# 48V_0_5A_Converter.net
KiCad netlist of a schematic drawn in Altium Designer
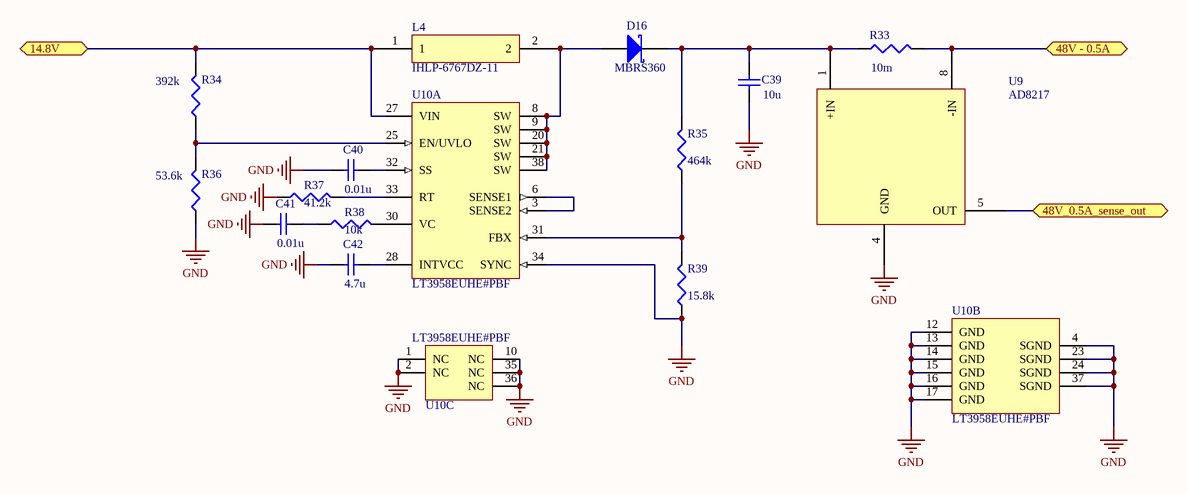
[diagram p0: 48V_0.5A_Converter.SchDoc]

(export (version "E")
  (design (tool "Eeschema 10.0.6"))
  (components
    (comp (ref "C39")
      (value "10u")
      (footprint "C1206")
      (description "Capacitor (Semiconductor SIM Model)")
      (fields (field (name "Comment") "Cap Semi") (field (name "PUBLISHER") "Altium Limited"))
      (libsource (lib "Miscellaneous Devices") (part "Cap Semi"))
    )
    (comp (ref "C40")
      (value "0.01u")
      (footprint "C1206")
      (description "Capacitor (Semiconductor SIM Model)")
      (fields (field (name "Comment") "Cap Semi") (field (name "PUBLISHER") "Altium Limited"))
      (libsource (lib "Miscellaneous Devices") (part "Cap Semi"))
    )
    (comp (ref "C41")
      (value "0.01u")
      (footprint "C1206")
      (description "Capacitor (Semiconductor SIM Model)")
      (fields (field (name "Comment") "Cap Semi") (field (name "PUBLISHER") "Altium Limited"))
      (libsource (lib "Miscellaneous Devices") (part "Cap Semi"))
    )
    (comp (ref "C42")
      (value "4.7u")
      (footprint "C1206")
      (description "Capacitor (Semiconductor SIM Model)")
      (fields (field (name "Comment") "Cap Semi") (field (name "PUBLISHER") "Altium Limited"))
      (libsource (lib "Miscellaneous Devices") (part "Cap Semi"))
    )
    (comp (ref "D16")
      (value "MBRS360")
      (footprint "SMB")
      (description "Schottky Diode")
      (fields (field (name "PUBLISHER") "Altium Limited"))
      (libsource (lib "Miscellaneous Devices") (part "D Schottky"))
    )
    (comp (ref "L4")
      (value "IHLP-6767DZ-11")
      (footprint "IHLP-6767DZ-11")
      (description "Inductor")
      (libsource (lib "Integrated_Library") (part "IHLP-6767DZ-11"))
    )
    (comp (ref "R33")
      (value "10m")
      (footprint "J1-0603")
      (description "Resistor")
      (fields (field (name "Comment") "Res3") (field (name "PUBLISHER") "Altium Limited"))
      (libsource (lib "Miscellaneous Devices") (part "Res3"))
    )
    (comp (ref "R34")
      (value "392k")
      (footprint "J1-0603")
      (description "Resistor")
      (fields (field (name "Comment") "Res3") (field (name "PUBLISHER") "Altium Limited"))
      (libsource (lib "Miscellaneous Devices") (part "Res3"))
    )
    (comp (ref "R35")
      (value "464k")
      (footprint "J1-0603")
      (description "Resistor")
      (fields (field (name "Comment") "Res3") (field (name "PUBLISHER") "Altium Limited"))
      (libsource (lib "Miscellaneous Devices") (part "Res3"))
    )
    (comp (ref "R36")
      (value "53.6k")
      (footprint "J1-0603")
      (description "Resistor")
      (fields (field (name "Comment") "Res3") (field (name "PUBLISHER") "Altium Limited"))
      (libsource (lib "Miscellaneous Devices") (part "Res3"))
    )
    (comp (ref "R37")
      (value "41.2k")
      (footprint "J1-0603")
      (description "Resistor")
      (fields (field (name "Comment") "Res3") (field (name "PUBLISHER") "Altium Limited"))
      (libsource (lib "Miscellaneous Devices") (part "Res3"))
    )
    (comp (ref "R38")
      (value "10k")
      (footprint "J1-0603")
      (description "Resistor")
      (fields (field (name "Comment") "Res3") (field (name "PUBLISHER") "Altium Limited"))
      (libsource (lib "Miscellaneous Devices") (part "Res3"))
    )
    (comp (ref "R39")
      (value "15.8k")
      (footprint "J1-0603")
      (description "Resistor")
      (fields (field (name "Comment") "Res3") (field (name "PUBLISHER") "Altium Limited"))
      (libsource (lib "Miscellaneous Devices") (part "Res3"))
    )
    (comp (ref "U9")
      (value "AD8217")
      (footprint "AD8217")
      (description "Current Shunt Moniter")
      (libsource (lib "Integrated_Library") (part "AD8217"))
    )
    (comp (ref "U10")
      (value "LT3958EUHE#PBF")
      (footprint "LT3958")
      (description "LT3958")
      (fields (field (name "MANUFACTURER") "Linear Technology"))
      (libsource (lib "Integrated_Library") (part "LT3958EUHE#PBF"))
    )
  )
  (nets
    (net (code "1") (name "/14.8V") (class "Default")
      (node (ref "L4") (pin "1") (pinfunction "1_1") (pintype "passive"))
      (node (ref "R34") (pin "2") (pinfunction "2_2") (pintype "passive"))
      (node (ref "U10") (pin "27") (pinfunction "VIN_27") (pintype "power_in"))
    )
    (net (code "2") (name "/48V - 0.5A") (class "Default")
      (node (ref "R33") (pin "2") (pinfunction "2_2") (pintype "passive"))
      (node (ref "U9") (pin "8") (pinfunction "-IN_8") (pintype "passive"))
    )
    (net (code "3") (name "/48V_0.5A_sense_out") (class "Default")
      (node (ref "U9") (pin "5") (pinfunction "OUT_5") (pintype "passive"))
    )
    (net (code "4") (name "GND") (class "Default")
      (node (ref "C39") (pin "1") (pinfunction "1_1") (pintype "passive"))
      (node (ref "C40") (pin "1") (pinfunction "1_1") (pintype "passive"))
      (node (ref "C41") (pin "1") (pinfunction "1_1") (pintype "passive"))
      (node (ref "C42") (pin "1") (pinfunction "1_1") (pintype "passive"))
      (node (ref "R36") (pin "1") (pinfunction "1_1") (pintype "passive"))
      (node (ref "R37") (pin "1") (pinfunction "1_1") (pintype "passive"))
      (node (ref "R39") (pin "1") (pinfunction "1_1") (pintype "passive"))
      (node (ref "U10") (pin "1") (pinfunction "NC_1") (pintype "passive"))
      (node (ref "U10") (pin "10") (pinfunction "NC_10") (pintype "passive"))
      (node (ref "U10") (pin "12") (pinfunction "GND_12") (pintype "power_in"))
      (node (ref "U10") (pin "13") (pinfunction "GND_13") (pintype "power_in"))
      (node (ref "U10") (pin "14") (pinfunction "GND_14") (pintype "power_in"))
      (node (ref "U10") (pin "15") (pinfunction "GND_15") (pintype "power_in"))
      (node (ref "U10") (pin "16") (pinfunction "GND_16") (pintype "power_in"))
      (node (ref "U10") (pin "17") (pinfunction "GND_17") (pintype "power_in"))
      (node (ref "U10") (pin "2") (pinfunction "NC_2") (pintype "passive"))
      (node (ref "U10") (pin "23") (pinfunction "SGND_23") (pintype "power_in"))
      (node (ref "U10") (pin "24") (pinfunction "SGND_24") (pintype "power_in"))
      (node (ref "U10") (pin "34") (pinfunction "SYNC_34") (pintype "input"))
      (node (ref "U10") (pin "35") (pinfunction "NC_35") (pintype "passive"))
      (node (ref "U10") (pin "36") (pinfunction "NC_36") (pintype "passive"))
      (node (ref "U10") (pin "37") (pinfunction "SGND_37") (pintype "power_in"))
      (node (ref "U10") (pin "4") (pinfunction "SGND_4") (pintype "power_in"))
      (node (ref "U9") (pin "4") (pinfunction "GND_4") (pintype "passive"))
    )
    (net (code "5") (name "Net-(C41-Pad2)") (class "Default")
      (node (ref "C41") (pin "2") (pinfunction "2_2") (pintype "passive"))
      (node (ref "R38") (pin "1") (pinfunction "1_1") (pintype "passive"))
    )
    (net (code "6") (name "Net-(D16-A)") (class "Default")
      (node (ref "D16") (pin "1") (pinfunction "A_1") (pintype "passive"))
      (node (ref "L4") (pin "2") (pinfunction "2_2") (pintype "passive"))
      (node (ref "U10") (pin "20") (pinfunction "SW_20") (pintype "power_in"))
      (node (ref "U10") (pin "21") (pinfunction "SW_21") (pintype "power_in"))
      (node (ref "U10") (pin "38") (pinfunction "SW_38") (pintype "power_in"))
      (node (ref "U10") (pin "8") (pinfunction "SW_8") (pintype "power_in"))
      (node (ref "U10") (pin "9") (pinfunction "SW_9") (pintype "power_in"))
    )
    (net (code "7") (name "Net-(D16-K)") (class "Default")
      (node (ref "C39") (pin "2") (pinfunction "2_2") (pintype "passive"))
      (node (ref "D16") (pin "2") (pinfunction "K_2") (pintype "passive"))
      (node (ref "R33") (pin "1") (pinfunction "1_1") (pintype "passive"))
      (node (ref "R35") (pin "2") (pinfunction "2_2") (pintype "passive"))
      (node (ref "U9") (pin "1") (pinfunction "+IN_1") (pintype "passive"))
    )
    (net (code "8") (name "Net-(U10A-EN{slash}UVLO)") (class "Default")
      (node (ref "R34") (pin "1") (pinfunction "1_1") (pintype "passive"))
      (node (ref "R36") (pin "2") (pinfunction "2_2") (pintype "passive"))
      (node (ref "U10") (pin "25") (pinfunction "EN/UVLO_25") (pintype "input"))
    )
    (net (code "9") (name "Net-(U10A-FBX)") (class "Default")
      (node (ref "R35") (pin "1") (pinfunction "1_1") (pintype "passive"))
      (node (ref "R39") (pin "2") (pinfunction "2_2") (pintype "passive"))
      (node (ref "U10") (pin "31") (pinfunction "FBX_31") (pintype "input"))
    )
    (net (code "10") (name "Net-(U10A-INTVCC)") (class "Default")
      (node (ref "C42") (pin "2") (pinfunction "2_2") (pintype "passive"))
      (node (ref "U10") (pin "28") (pinfunction "INTVCC_28") (pintype "power_in"))
    )
    (net (code "11") (name "Net-(U10A-RT)") (class "Default")
      (node (ref "R37") (pin "2") (pinfunction "2_2") (pintype "passive"))
      (node (ref "U10") (pin "33") (pinfunction "RT_33") (pintype "passive"))
    )
    (net (code "12") (name "Net-(U10A-SENSE1)") (class "Default")
      (node (ref "U10") (pin "3") (pinfunction "SENSE2_3") (pintype "input"))
      (node (ref "U10") (pin "6") (pinfunction "SENSE1_6") (pintype "output"))
    )
    (net (code "13") (name "Net-(U10A-SS)") (class "Default")
      (node (ref "C40") (pin "2") (pinfunction "2_2") (pintype "passive"))
      (node (ref "U10") (pin "32") (pinfunction "SS_32") (pintype "input"))
    )
    (net (code "14") (name "Net-(U10A-VC)") (class "Default")
      (node (ref "R38") (pin "2") (pinfunction "2_2") (pintype "passive"))
      (node (ref "U10") (pin "30") (pinfunction "VC_30") (pintype "passive"))
    )
  )
)
